# MachXO2_eval.net
KiCad netlist of a schematic drawn in EAGLE
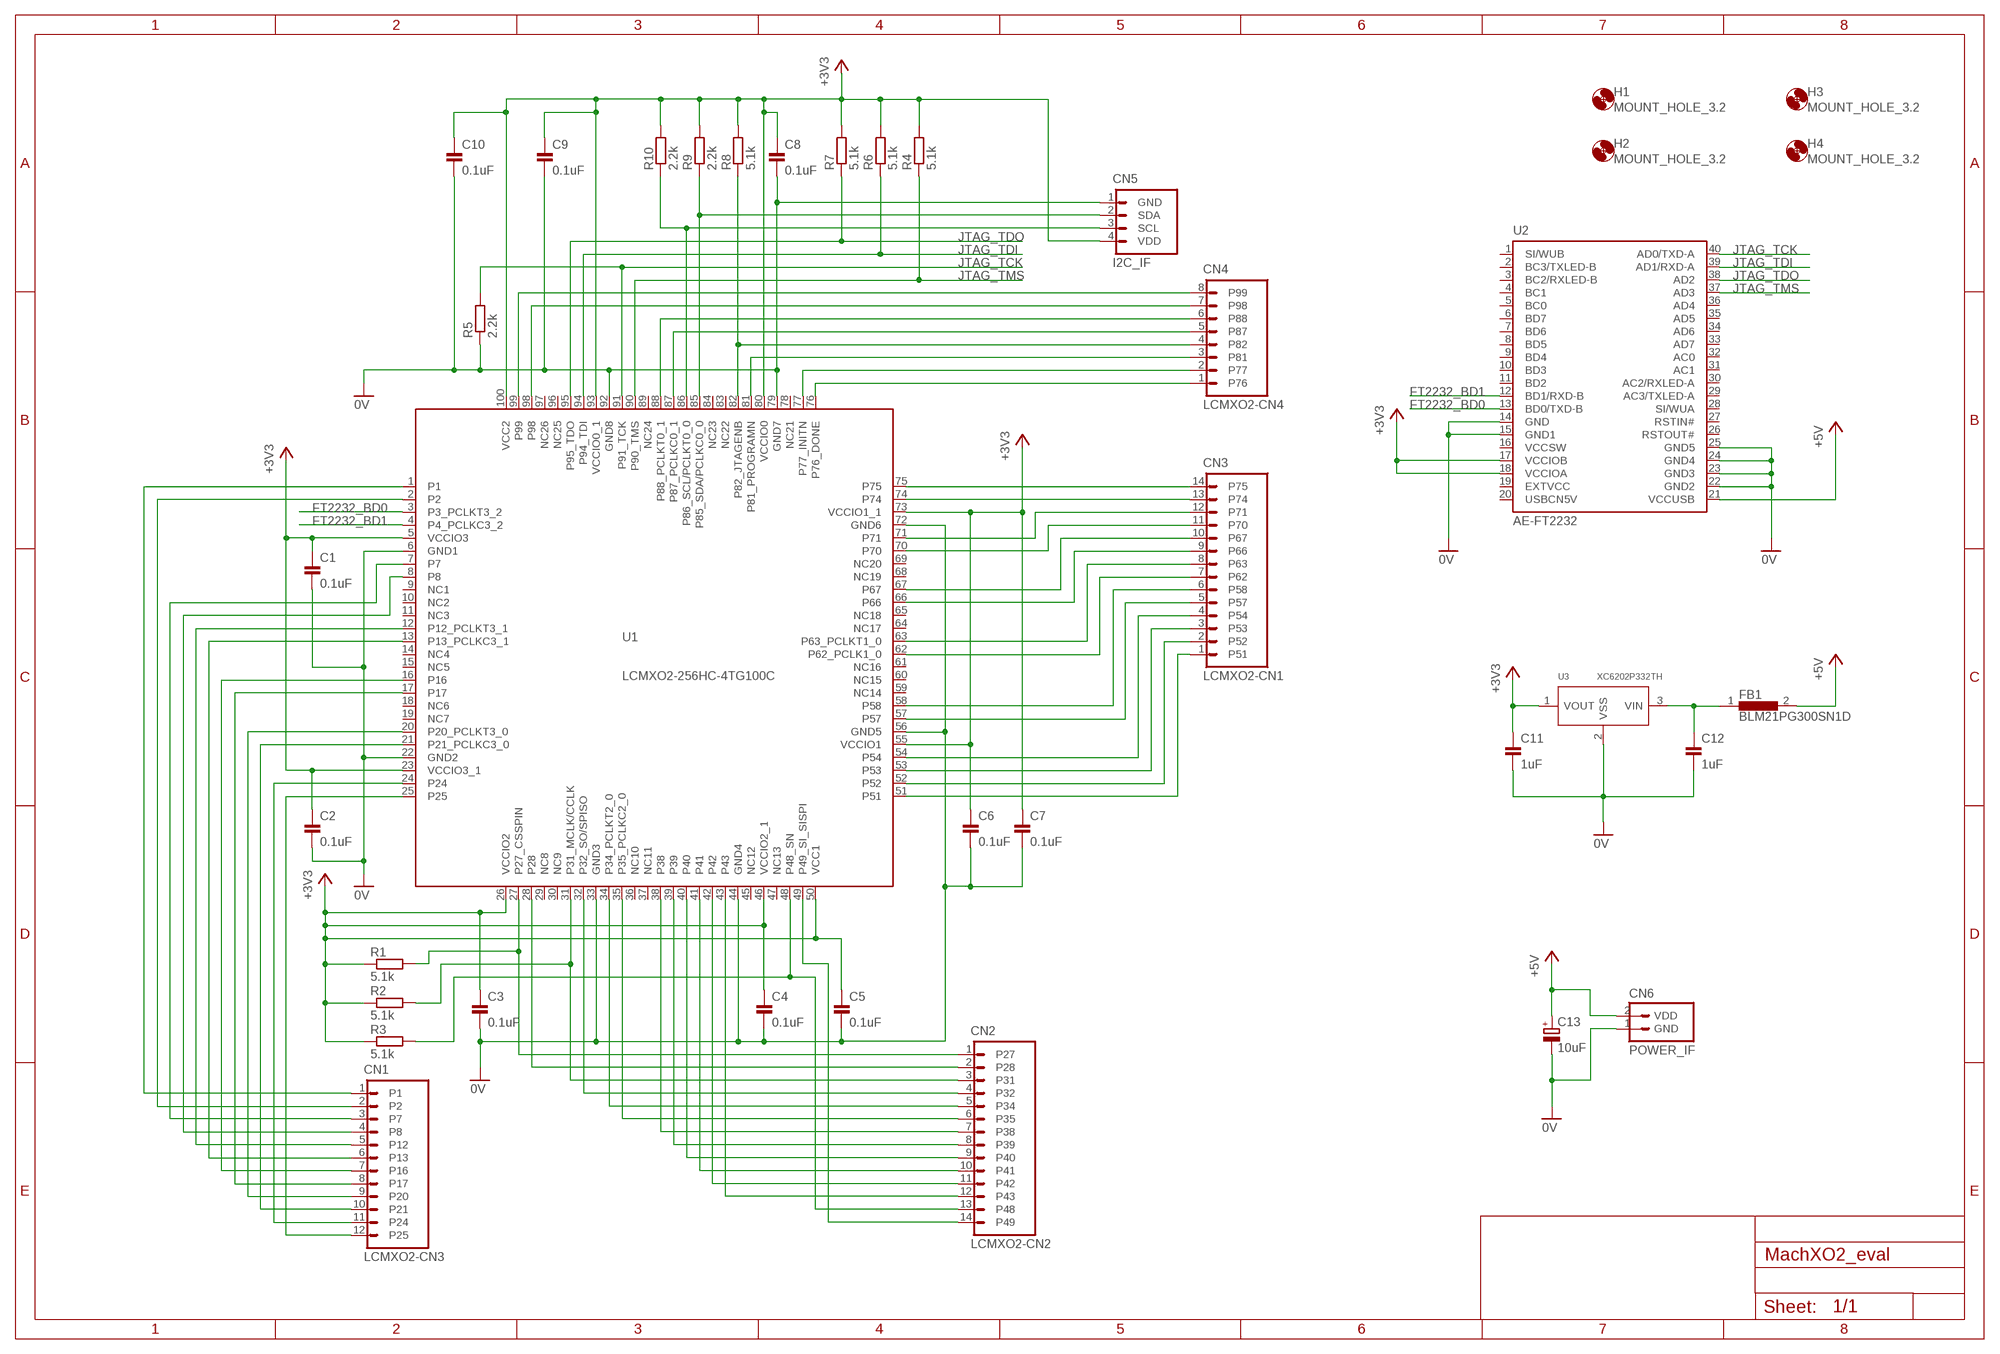
[diagram p0: schematic, sheet 1]

(export (version "E")
  (design (tool "Eeschema 10.0.6"))
  (components
    (comp (ref "C1")
      (value "0.1uF")
      (footprint "eagle-import:CAP_100MIL")
      (libsource (lib "eagle-import") (part "CAP_100MIL"))
    )
    (comp (ref "C2")
      (value "0.1uF")
      (footprint "eagle-import:CAP_100MIL")
      (libsource (lib "eagle-import") (part "CAP_100MIL"))
    )
    (comp (ref "C3")
      (value "0.1uF")
      (footprint "eagle-import:CAP_100MIL")
      (libsource (lib "eagle-import") (part "CAP_100MIL"))
    )
    (comp (ref "C4")
      (value "0.1uF")
      (footprint "eagle-import:CAP_100MIL")
      (libsource (lib "eagle-import") (part "CAP_100MIL"))
    )
    (comp (ref "C5")
      (value "0.1uF")
      (footprint "eagle-import:CAP_100MIL")
      (libsource (lib "eagle-import") (part "CAP_100MIL"))
    )
    (comp (ref "C6")
      (value "0.1uF")
      (footprint "eagle-import:CAP_100MIL")
      (libsource (lib "eagle-import") (part "CAP_100MIL"))
    )
    (comp (ref "C7")
      (value "0.1uF")
      (footprint "eagle-import:CAP_100MIL")
      (libsource (lib "eagle-import") (part "CAP_100MIL"))
    )
    (comp (ref "C8")
      (value "0.1uF")
      (footprint "eagle-import:CAP_100MIL")
      (libsource (lib "eagle-import") (part "CAP_100MIL"))
    )
    (comp (ref "C9")
      (value "0.1uF")
      (footprint "eagle-import:CAP_100MIL")
      (libsource (lib "eagle-import") (part "CAP_100MIL"))
    )
    (comp (ref "C10")
      (value "0.1uF")
      (footprint "eagle-import:CAP_100MIL")
      (libsource (lib "eagle-import") (part "CAP_100MIL"))
    )
    (comp (ref "C11")
      (value "1uF")
      (footprint "eagle-import:CAP_200MIL")
      (libsource (lib "eagle-import") (part "CAP_200MIL"))
    )
    (comp (ref "C12")
      (value "1uF")
      (footprint "eagle-import:CAP_200MIL")
      (libsource (lib "eagle-import") (part "CAP_200MIL"))
    )
    (comp (ref "C13")
      (value "10uF")
      (footprint "eagle-import:ELECAP_200MIL")
      (libsource (lib "eagle-import") (part "ELECAP_200MIL"))
    )
    (comp (ref "CN1")
      (value "LCMXO2-CN3")
      (footprint "eagle-import:LCMXO2-CN-3")
      (libsource (lib "eagle-import") (part "LCMXO2-CN3"))
    )
    (comp (ref "CN2")
      (value "LCMXO2-CN2")
      (footprint "eagle-import:LCMXO2-CN-2")
      (libsource (lib "eagle-import") (part "LCMXO2-CN2"))
    )
    (comp (ref "CN3")
      (value "LCMXO2-CN1")
      (footprint "eagle-import:LCMXO2-CN-1")
      (libsource (lib "eagle-import") (part "LCMXO2-CN1"))
    )
    (comp (ref "CN4")
      (value "LCMXO2-CN4")
      (footprint "eagle-import:LCMXO2-CN-4")
      (libsource (lib "eagle-import") (part "LCMXO2-CN4"))
    )
    (comp (ref "CN5")
      (value "I2C_IF")
      (footprint "eagle-import:I2C_IF_4PIN")
      (libsource (lib "eagle-import") (part "I2C_IF"))
    )
    (comp (ref "CN6")
      (value "POWER_IF")
      (footprint "eagle-import:HEADER_2PIN_POWER_IF")
      (libsource (lib "eagle-import") (part "POWER_IF"))
    )
    (comp (ref "FB1")
      (value "BLM21PG300SN1D")
      (footprint "eagle-import:SMD_2012")
      (libsource (lib "eagle-import") (part "BLM21PG300SN1D"))
    )
    (comp (ref "H1")
      (value "MOUNT_HOLE_3.2")
      (footprint "eagle-import:3,2")
      (libsource (lib "eagle-import") (part "MOUNT_HOLE_3.2"))
    )
    (comp (ref "H2")
      (value "MOUNT_HOLE_3.2")
      (footprint "eagle-import:3,2")
      (libsource (lib "eagle-import") (part "MOUNT_HOLE_3.2"))
    )
    (comp (ref "H3")
      (value "MOUNT_HOLE_3.2")
      (footprint "eagle-import:3,2")
      (libsource (lib "eagle-import") (part "MOUNT_HOLE_3.2"))
    )
    (comp (ref "H4")
      (value "MOUNT_HOLE_3.2")
      (footprint "eagle-import:3,2")
      (libsource (lib "eagle-import") (part "MOUNT_HOLE_3.2"))
    )
    (comp (ref "R1")
      (value "5.1k")
      (footprint "eagle-import:RESISTOR_0204_200MIL")
      (libsource (lib "eagle-import") (part "RESISTOR_200MIL"))
    )
    (comp (ref "R2")
      (value "5.1k")
      (footprint "eagle-import:RESISTOR_0204_200MIL")
      (libsource (lib "eagle-import") (part "RESISTOR_200MIL"))
    )
    (comp (ref "R3")
      (value "5.1k")
      (footprint "eagle-import:RESISTOR_0204_200MIL")
      (libsource (lib "eagle-import") (part "RESISTOR_200MIL"))
    )
    (comp (ref "R4")
      (value "5.1k")
      (footprint "eagle-import:RESISTOR_0204_200MIL")
      (libsource (lib "eagle-import") (part "RESISTOR_200MIL"))
    )
    (comp (ref "R5")
      (value "2.2k")
      (footprint "eagle-import:RESISTOR_0204_200MIL")
      (libsource (lib "eagle-import") (part "RESISTOR_200MIL"))
    )
    (comp (ref "R6")
      (value "5.1k")
      (footprint "eagle-import:RESISTOR_0204_200MIL")
      (libsource (lib "eagle-import") (part "RESISTOR_200MIL"))
    )
    (comp (ref "R7")
      (value "5.1k")
      (footprint "eagle-import:RESISTOR_0204_200MIL")
      (libsource (lib "eagle-import") (part "RESISTOR_200MIL"))
    )
    (comp (ref "R8")
      (value "5.1k")
      (footprint "eagle-import:RESISTOR_0204_200MIL")
      (libsource (lib "eagle-import") (part "RESISTOR_200MIL"))
    )
    (comp (ref "R9")
      (value "2.2k")
      (footprint "eagle-import:RESISTOR_0204_200MIL")
      (libsource (lib "eagle-import") (part "RESISTOR_200MIL"))
    )
    (comp (ref "R10")
      (value "2.2k")
      (footprint "eagle-import:RESISTOR_0204_200MIL")
      (libsource (lib "eagle-import") (part "RESISTOR_200MIL"))
    )
    (comp (ref "U1")
      (value "LCMXO2-256HC-4TG100C")
      (footprint "eagle-import:QFP100-0.5MMPITCH")
      (libsource (lib "eagle-import") (part "LCMXO2-256HC-4TG100C"))
    )
    (comp (ref "U2")
      (value "AE-FT2232")
      (footprint "eagle-import:DIL40")
      (libsource (lib "eagle-import") (part "AE-FT2232"))
    )
    (comp (ref "U3")
      (value "XC6202P332TH")
      (footprint "eagle-import:TO92-LINE")
      (libsource (lib "eagle-import") (part "XC6202P332TH"))
    )
  )
  (nets
    (net (code "1") (name "+3V3") (class "Default")
      (node (ref "C1") (pin "1") (pinfunction "1_1") (pintype "passive"))
      (node (ref "C10") (pin "1") (pinfunction "1_1") (pintype "passive"))
      (node (ref "C11") (pin "1") (pinfunction "1_1") (pintype "passive"))
      (node (ref "C2") (pin "1") (pinfunction "1_1") (pintype "passive"))
      (node (ref "C3") (pin "1") (pinfunction "1_1") (pintype "passive"))
      (node (ref "C4") (pin "1") (pinfunction "1_1") (pintype "passive"))
      (node (ref "C5") (pin "1") (pinfunction "1_1") (pintype "passive"))
      (node (ref "C6") (pin "1") (pinfunction "1_1") (pintype "passive"))
      (node (ref "C7") (pin "1") (pinfunction "1_1") (pintype "passive"))
      (node (ref "C8") (pin "1") (pinfunction "1_1") (pintype "passive"))
      (node (ref "C9") (pin "1") (pinfunction "1_1") (pintype "passive"))
      (node (ref "CN5") (pin "4") (pinfunction "VDD_4") (pintype "passive"))
      (node (ref "R1") (pin "1") (pinfunction "1_1") (pintype "passive"))
      (node (ref "R10") (pin "2") (pinfunction "2_2") (pintype "passive"))
      (node (ref "R2") (pin "1") (pinfunction "1_1") (pintype "passive"))
      (node (ref "R3") (pin "1") (pinfunction "1_1") (pintype "passive"))
      (node (ref "R4") (pin "2") (pinfunction "2_2") (pintype "passive"))
      (node (ref "R6") (pin "2") (pinfunction "2_2") (pintype "passive"))
      (node (ref "R7") (pin "2") (pinfunction "2_2") (pintype "passive"))
      (node (ref "R8") (pin "2") (pinfunction "2_2") (pintype "passive"))
      (node (ref "R9") (pin "2") (pinfunction "2_2") (pintype "passive"))
      (node (ref "U1") (pin "100") (pinfunction "VCC2_100") (pintype "passive"))
      (node (ref "U1") (pin "23") (pinfunction "VCCIO3_1_23") (pintype "passive"))
      (node (ref "U1") (pin "26") (pinfunction "VCCIO2_26") (pintype "passive"))
      (node (ref "U1") (pin "46") (pinfunction "VCCIO2_1_46") (pintype "passive"))
      (node (ref "U1") (pin "5") (pinfunction "VCCIO3_5") (pintype "passive"))
      (node (ref "U1") (pin "50") (pinfunction "VCC1_50") (pintype "passive"))
      (node (ref "U1") (pin "55") (pinfunction "VCCIO1_55") (pintype "passive"))
      (node (ref "U1") (pin "73") (pinfunction "VCCIO1_1_73") (pintype "passive"))
      (node (ref "U1") (pin "80") (pinfunction "VCCIO0_80") (pintype "passive"))
      (node (ref "U1") (pin "93") (pinfunction "VCCIO0_1_93") (pintype "passive"))
      (node (ref "U2") (pin "17") (pinfunction "VCCIOB_17") (pintype "passive"))
      (node (ref "U2") (pin "18") (pinfunction "VCCIOA_18") (pintype "passive"))
      (node (ref "U3") (pin "1") (pinfunction "VOUT_1") (pintype "passive"))
    )
    (net (code "2") (name "+5V") (class "Default")
      (node (ref "C13") (pin "+") (pinfunction "+_+") (pintype "passive"))
      (node (ref "CN6") (pin "2") (pinfunction "VDD_2") (pintype "passive"))
      (node (ref "FB1") (pin "2") (pinfunction "2_2") (pintype "passive"))
      (node (ref "U2") (pin "21") (pinfunction "VCCUSB_21") (pintype "passive"))
    )
    (net (code "3") (name "/FT2232_BD0") (class "Default")
      (node (ref "U1") (pin "3") (pinfunction "P3_PCLKT3_2_3") (pintype "bidirectional"))
      (node (ref "U2") (pin "13") (pinfunction "BD0/TXD-B_13") (pintype "bidirectional"))
    )
    (net (code "4") (name "/FT2232_BD1") (class "Default")
      (node (ref "U1") (pin "4") (pinfunction "P4_PCLKC3_2_4") (pintype "bidirectional"))
      (node (ref "U2") (pin "12") (pinfunction "BD1/RXD-B_12") (pintype "bidirectional"))
    )
    (net (code "5") (name "/JTAG_TCK") (class "Default")
      (node (ref "R5") (pin "2") (pinfunction "2_2") (pintype "passive"))
      (node (ref "U1") (pin "91") (pinfunction "P91_TCK_91") (pintype "bidirectional"))
      (node (ref "U2") (pin "40") (pinfunction "AD0/TXD-A_40") (pintype "bidirectional"))
    )
    (net (code "6") (name "/JTAG_TDI") (class "Default")
      (node (ref "R6") (pin "1") (pinfunction "1_1") (pintype "passive"))
      (node (ref "U1") (pin "94") (pinfunction "P94_TDI_94") (pintype "bidirectional"))
      (node (ref "U2") (pin "39") (pinfunction "AD1/RXD-A_39") (pintype "bidirectional"))
    )
    (net (code "7") (name "/JTAG_TDO") (class "Default")
      (node (ref "R7") (pin "1") (pinfunction "1_1") (pintype "passive"))
      (node (ref "U1") (pin "95") (pinfunction "P95_TDO_95") (pintype "bidirectional"))
      (node (ref "U2") (pin "38") (pinfunction "AD2_38") (pintype "bidirectional"))
    )
    (net (code "8") (name "/JTAG_TMS") (class "Default")
      (node (ref "R4") (pin "1") (pinfunction "1_1") (pintype "passive"))
      (node (ref "U1") (pin "90") (pinfunction "P90_TMS_90") (pintype "bidirectional"))
      (node (ref "U2") (pin "37") (pinfunction "AD3_37") (pintype "bidirectional"))
    )
    (net (code "9") (name "0V") (class "Default")
      (node (ref "C1") (pin "2") (pinfunction "2_2") (pintype "passive"))
      (node (ref "C10") (pin "2") (pinfunction "2_2") (pintype "passive"))
      (node (ref "C11") (pin "2") (pinfunction "2_2") (pintype "passive"))
      (node (ref "C12") (pin "2") (pinfunction "2_2") (pintype "passive"))
      (node (ref "C13") (pin "-") (pinfunction "-_-") (pintype "passive"))
      (node (ref "C2") (pin "2") (pinfunction "2_2") (pintype "passive"))
      (node (ref "C3") (pin "2") (pinfunction "2_2") (pintype "passive"))
      (node (ref "C4") (pin "2") (pinfunction "2_2") (pintype "passive"))
      (node (ref "C5") (pin "2") (pinfunction "2_2") (pintype "passive"))
      (node (ref "C6") (pin "2") (pinfunction "2_2") (pintype "passive"))
      (node (ref "C7") (pin "2") (pinfunction "2_2") (pintype "passive"))
      (node (ref "C8") (pin "2") (pinfunction "2_2") (pintype "passive"))
      (node (ref "C9") (pin "2") (pinfunction "2_2") (pintype "passive"))
      (node (ref "CN5") (pin "1") (pinfunction "GND_1") (pintype "passive"))
      (node (ref "CN6") (pin "1") (pinfunction "GND_1") (pintype "passive"))
      (node (ref "R5") (pin "1") (pinfunction "1_1") (pintype "passive"))
      (node (ref "U1") (pin "22") (pinfunction "GND2_22") (pintype "passive"))
      (node (ref "U1") (pin "33") (pinfunction "GND3_33") (pintype "passive"))
      (node (ref "U1") (pin "44") (pinfunction "GND4_44") (pintype "passive"))
      (node (ref "U1") (pin "56") (pinfunction "GND5_56") (pintype "passive"))
      (node (ref "U1") (pin "6") (pinfunction "GND1_6") (pintype "passive"))
      (node (ref "U1") (pin "72") (pinfunction "GND6_72") (pintype "passive"))
      (node (ref "U1") (pin "79") (pinfunction "GND7_79") (pintype "passive"))
      (node (ref "U1") (pin "92") (pinfunction "GND8_92") (pintype "passive"))
      (node (ref "U2") (pin "14") (pinfunction "GND_14") (pintype "passive"))
      (node (ref "U2") (pin "15") (pinfunction "GND1_15") (pintype "passive"))
      (node (ref "U2") (pin "22") (pinfunction "GND2_22") (pintype "passive"))
      (node (ref "U2") (pin "23") (pinfunction "GND3_23") (pintype "passive"))
      (node (ref "U2") (pin "24") (pinfunction "GND4_24") (pintype "passive"))
      (node (ref "U2") (pin "25") (pinfunction "GND5_25") (pintype "passive"))
      (node (ref "U3") (pin "2") (pinfunction "VSS_2") (pintype "passive"))
    )
    (net (code "10") (name "Net-(CN1-P1)") (class "Default")
      (node (ref "CN1") (pin "1") (pinfunction "P1_1") (pintype "bidirectional"))
      (node (ref "U1") (pin "1") (pinfunction "P1_1") (pintype "bidirectional"))
    )
    (net (code "11") (name "Net-(CN1-P2)") (class "Default")
      (node (ref "CN1") (pin "2") (pinfunction "P2_2") (pintype "bidirectional"))
      (node (ref "U1") (pin "2") (pinfunction "P2_2") (pintype "bidirectional"))
    )
    (net (code "12") (name "Net-(CN1-P7)") (class "Default")
      (node (ref "CN1") (pin "3") (pinfunction "P7_3") (pintype "bidirectional"))
      (node (ref "U1") (pin "7") (pinfunction "P7_7") (pintype "bidirectional"))
    )
    (net (code "13") (name "Net-(CN1-P8)") (class "Default")
      (node (ref "CN1") (pin "4") (pinfunction "P8_4") (pintype "bidirectional"))
      (node (ref "U1") (pin "8") (pinfunction "P8_8") (pintype "bidirectional"))
    )
    (net (code "14") (name "Net-(CN1-P12)") (class "Default")
      (node (ref "CN1") (pin "5") (pinfunction "P12_5") (pintype "bidirectional"))
      (node (ref "U1") (pin "12") (pinfunction "P12_PCLKT3_1_12") (pintype "bidirectional"))
    )
    (net (code "15") (name "Net-(CN1-P13)") (class "Default")
      (node (ref "CN1") (pin "6") (pinfunction "P13_6") (pintype "bidirectional"))
      (node (ref "U1") (pin "13") (pinfunction "P13_PCLKC3_1_13") (pintype "bidirectional"))
    )
    (net (code "16") (name "Net-(CN1-P16)") (class "Default")
      (node (ref "CN1") (pin "7") (pinfunction "P16_7") (pintype "bidirectional"))
      (node (ref "U1") (pin "16") (pinfunction "P16_16") (pintype "bidirectional"))
    )
    (net (code "17") (name "Net-(CN1-P17)") (class "Default")
      (node (ref "CN1") (pin "8") (pinfunction "P17_8") (pintype "bidirectional"))
      (node (ref "U1") (pin "17") (pinfunction "P17_17") (pintype "bidirectional"))
    )
    (net (code "18") (name "Net-(CN1-P20)") (class "Default")
      (node (ref "CN1") (pin "9") (pinfunction "P20_9") (pintype "bidirectional"))
      (node (ref "U1") (pin "20") (pinfunction "P20_PCLKT3_0_20") (pintype "bidirectional"))
    )
    (net (code "19") (name "Net-(CN1-P21)") (class "Default")
      (node (ref "CN1") (pin "10") (pinfunction "P21_10") (pintype "bidirectional"))
      (node (ref "U1") (pin "21") (pinfunction "P21_PCLKC3_0_21") (pintype "bidirectional"))
    )
    (net (code "20") (name "Net-(CN1-P24)") (class "Default")
      (node (ref "CN1") (pin "11") (pinfunction "P24_11") (pintype "bidirectional"))
      (node (ref "U1") (pin "24") (pinfunction "P24_24") (pintype "bidirectional"))
    )
    (net (code "21") (name "Net-(CN1-P25)") (class "Default")
      (node (ref "CN1") (pin "12") (pinfunction "P25_12") (pintype "bidirectional"))
      (node (ref "U1") (pin "25") (pinfunction "P25_25") (pintype "bidirectional"))
    )
    (net (code "22") (name "Net-(CN2-P27)") (class "Default")
      (node (ref "CN2") (pin "1") (pinfunction "P27_1") (pintype "bidirectional"))
      (node (ref "R1") (pin "2") (pinfunction "2_2") (pintype "passive"))
      (node (ref "U1") (pin "27") (pinfunction "P27_CSSPIN_27") (pintype "bidirectional"))
    )
    (net (code "23") (name "Net-(CN2-P28)") (class "Default")
      (node (ref "CN2") (pin "2") (pinfunction "P28_2") (pintype "bidirectional"))
      (node (ref "U1") (pin "28") (pinfunction "P28_28") (pintype "bidirectional"))
    )
    (net (code "24") (name "Net-(CN2-P31)") (class "Default")
      (node (ref "CN2") (pin "3") (pinfunction "P31_3") (pintype "bidirectional"))
      (node (ref "R2") (pin "2") (pinfunction "2_2") (pintype "passive"))
      (node (ref "U1") (pin "31") (pinfunction "P31_MCLK/CCLK_31") (pintype "bidirectional"))
    )
    (net (code "25") (name "Net-(CN2-P32)") (class "Default")
      (node (ref "CN2") (pin "4") (pinfunction "P32_4") (pintype "bidirectional"))
      (node (ref "U1") (pin "32") (pinfunction "P32_SO/SPISO_32") (pintype "bidirectional"))
    )
    (net (code "26") (name "Net-(CN2-P34)") (class "Default")
      (node (ref "CN2") (pin "5") (pinfunction "P34_5") (pintype "bidirectional"))
      (node (ref "U1") (pin "34") (pinfunction "P34_PCLKT2_0_34") (pintype "bidirectional"))
    )
    (net (code "27") (name "Net-(CN2-P35)") (class "Default")
      (node (ref "CN2") (pin "6") (pinfunction "P35_6") (pintype "bidirectional"))
      (node (ref "U1") (pin "35") (pinfunction "P35_PCLKC2_0_35") (pintype "bidirectional"))
    )
    (net (code "28") (name "Net-(CN2-P38)") (class "Default")
      (node (ref "CN2") (pin "7") (pinfunction "P38_7") (pintype "bidirectional"))
      (node (ref "U1") (pin "38") (pinfunction "P38_38") (pintype "bidirectional"))
    )
    (net (code "29") (name "Net-(CN2-P39)") (class "Default")
      (node (ref "CN2") (pin "8") (pinfunction "P39_8") (pintype "bidirectional"))
      (node (ref "U1") (pin "39") (pinfunction "P39_39") (pintype "bidirectional"))
    )
    (net (code "30") (name "Net-(CN2-P40)") (class "Default")
      (node (ref "CN2") (pin "9") (pinfunction "P40_9") (pintype "bidirectional"))
      (node (ref "U1") (pin "40") (pinfunction "P40_40") (pintype "bidirectional"))
    )
    (net (code "31") (name "Net-(CN2-P41)") (class "Default")
      (node (ref "CN2") (pin "10") (pinfunction "P41_10") (pintype "bidirectional"))
      (node (ref "U1") (pin "41") (pinfunction "P41_41") (pintype "bidirectional"))
    )
    (net (code "32") (name "Net-(CN2-P42)") (class "Default")
      (node (ref "CN2") (pin "11") (pinfunction "P42_11") (pintype "bidirectional"))
      (node (ref "U1") (pin "42") (pinfunction "P42_42") (pintype "bidirectional"))
    )
    (net (code "33") (name "Net-(CN2-P43)") (class "Default")
      (node (ref "CN2") (pin "12") (pinfunction "P43_12") (pintype "bidirectional"))
      (node (ref "U1") (pin "43") (pinfunction "P43_43") (pintype "bidirectional"))
    )
    (net (code "34") (name "Net-(CN2-P48)") (class "Default")
      (node (ref "CN2") (pin "13") (pinfunction "P48_13") (pintype "bidirectional"))
      (node (ref "R3") (pin "2") (pinfunction "2_2") (pintype "passive"))
      (node (ref "U1") (pin "48") (pinfunction "P48_SN_48") (pintype "bidirectional"))
    )
    (net (code "35") (name "Net-(CN2-P49)") (class "Default")
      (node (ref "CN2") (pin "14") (pinfunction "P49_14") (pintype "bidirectional"))
      (node (ref "U1") (pin "49") (pinfunction "P49_SI_SISPI_49") (pintype "bidirectional"))
    )
    (net (code "36") (name "Net-(CN3-P51)") (class "Default")
      (node (ref "CN3") (pin "1") (pinfunction "P51_1") (pintype "bidirectional"))
      (node (ref "U1") (pin "51") (pinfunction "P51_51") (pintype "bidirectional"))
    )
    (net (code "37") (name "Net-(CN3-P52)") (class "Default")
      (node (ref "CN3") (pin "2") (pinfunction "P52_2") (pintype "bidirectional"))
      (node (ref "U1") (pin "52") (pinfunction "P52_52") (pintype "bidirectional"))
    )
    (net (code "38") (name "Net-(CN3-P53)") (class "Default")
      (node (ref "CN3") (pin "3") (pinfunction "P53_3") (pintype "bidirectional"))
      (node (ref "U1") (pin "53") (pinfunction "P53_53") (pintype "bidirectional"))
    )
    (net (code "39") (name "Net-(CN3-P54)") (class "Default")
      (node (ref "CN3") (pin "4") (pinfunction "P54_4") (pintype "bidirectional"))
      (node (ref "U1") (pin "54") (pinfunction "P54_54") (pintype "bidirectional"))
    )
    (net (code "40") (name "Net-(CN3-P57)") (class "Default")
      (node (ref "CN3") (pin "5") (pinfunction "P57_5") (pintype "bidirectional"))
      (node (ref "U1") (pin "57") (pinfunction "P57_57") (pintype "bidirectional"))
    )
    (net (code "41") (name "Net-(CN3-P58)") (class "Default")
      (node (ref "CN3") (pin "6") (pinfunction "P58_6") (pintype "bidirectional"))
      (node (ref "U1") (pin "58") (pinfunction "P58_58") (pintype "bidirectional"))
    )
    (net (code "42") (name "Net-(CN3-P62)") (class "Default")
      (node (ref "CN3") (pin "7") (pinfunction "P62_7") (pintype "bidirectional"))
      (node (ref "U1") (pin "62") (pinfunction "P62_PCLK1_0_62") (pintype "bidirectional"))
    )
    (net (code "43") (name "Net-(CN3-P63)") (class "Default")
      (node (ref "CN3") (pin "8") (pinfunction "P63_8") (pintype "bidirectional"))
      (node (ref "U1") (pin "63") (pinfunction "P63_PCLKT1_0_63") (pintype "bidirectional"))
    )
    (net (code "44") (name "Net-(CN3-P66)") (class "Default")
      (node (ref "CN3") (pin "9") (pinfunction "P66_9") (pintype "bidirectional"))
      (node (ref "U1") (pin "66") (pinfunction "P66_66") (pintype "bidirectional"))
    )
    (net (code "45") (name "Net-(CN3-P67)") (class "Default")
      (node (ref "CN3") (pin "10") (pinfunction "P67_10") (pintype "bidirectional"))
      (node (ref "U1") (pin "67") (pinfunction "P67_67") (pintype "bidirectional"))
    )
    (net (code "46") (name "Net-(CN3-P70)") (class "Default")
      (node (ref "CN3") (pin "11") (pinfunction "P70_11") (pintype "bidirectional"))
      (node (ref "U1") (pin "70") (pinfunction "P70_70") (pintype "bidirectional"))
    )
    (net (code "47") (name "Net-(CN3-P71)") (class "Default")
      (node (ref "CN3") (pin "12") (pinfunction "P71_12") (pintype "bidirectional"))
      (node (ref "U1") (pin "71") (pinfunction "P71_71") (pintype "bidirectional"))
    )
    (net (code "48") (name "Net-(CN3-P74)") (class "Default")
      (node (ref "CN3") (pin "13") (pinfunction "P74_13") (pintype "bidirectional"))
      (node (ref "U1") (pin "74") (pinfunction "P74_74") (pintype "bidirectional"))
    )
    (net (code "49") (name "Net-(CN3-P75)") (class "Default")
      (node (ref "CN3") (pin "14") (pinfunction "P75_14") (pintype "bidirectional"))
      (node (ref "U1") (pin "75") (pinfunction "P75_75") (pintype "bidirectional"))
    )
    (net (code "50") (name "Net-(CN4-P76)") (class "Default")
      (node (ref "CN4") (pin "1") (pinfunction "P76_1") (pintype "bidirectional"))
      (node (ref "U1") (pin "76") (pinfunction "P76_DONE_76") (pintype "bidirectional"))
    )
    (net (code "51") (name "Net-(CN4-P77)") (class "Default")
      (node (ref "CN4") (pin "2") (pinfunction "P77_2") (pintype "bidirectional"))
      (node (ref "U1") (pin "77") (pinfunction "P77_INITN_77") (pintype "bidirectional"))
    )
    (net (code "52") (name "Net-(CN4-P81)") (class "Default")
      (node (ref "CN4") (pin "3") (pinfunction "P81_3") (pintype "bidirectional"))
      (node (ref "U1") (pin "81") (pinfunction "P81_PROGRAMN_81") (pintype "bidirectional"))
    )
    (net (code "53") (name "Net-(CN4-P82)") (class "Default")
      (node (ref "CN4") (pin "4") (pinfunction "P82_4") (pintype "bidirectional"))
      (node (ref "R8") (pin "1") (pinfunction "1_1") (pintype "passive"))
      (node (ref "U1") (pin "82") (pinfunction "P82_JTAGENB_82") (pintype "bidirectional"))
    )
    (net (code "54") (name "Net-(CN4-P87)") (class "Default")
      (node (ref "CN4") (pin "5") (pinfunction "P87_5") (pintype "bidirectional"))
      (node (ref "U1") (pin "87") (pinfunction "P87_PCLKC0_1_87") (pintype "bidirectional"))
    )
    (net (code "55") (name "Net-(CN4-P88)") (class "Default")
      (node (ref "CN4") (pin "6") (pinfunction "P88_6") (pintype "bidirectional"))
      (node (ref "U1") (pin "88") (pinfunction "P88_PCLKT0_1_88") (pintype "bidirectional"))
    )
    (net (code "56") (name "Net-(CN4-P98)") (class "Default")
      (node (ref "CN4") (pin "7") (pinfunction "P98_7") (pintype "bidirectional"))
      (node (ref "U1") (pin "98") (pinfunction "P98_98") (pintype "bidirectional"))
    )
    (net (code "57") (name "Net-(CN4-P99)") (class "Default")
      (node (ref "CN4") (pin "8") (pinfunction "P99_8") (pintype "bidirectional"))
      (node (ref "U1") (pin "99") (pinfunction "P99_99") (pintype "bidirectional"))
    )
    (net (code "58") (name "Net-(CN5-SCL)") (class "Default")
      (node (ref "CN5") (pin "3") (pinfunction "SCL_3") (pintype "bidirectional"))
      (node (ref "R10") (pin "1") (pinfunction "1_1") (pintype "passive"))
      (node (ref "U1") (pin "86") (pinfunction "P86_SCL/PCLKT0_0_86") (pintype "bidirectional"))
    )
    (net (code "59") (name "Net-(CN5-SDA)") (class "Default")
      (node (ref "CN5") (pin "2") (pinfunction "SDA_2") (pintype "bidirectional"))
      (node (ref "R9") (pin "1") (pinfunction "1_1") (pintype "passive"))
      (node (ref "U1") (pin "85") (pinfunction "P85_SDA/PCLKC0_0_85") (pintype "bidirectional"))
    )
    (net (code "60") (name "Net-(U3-VIN)") (class "Default")
      (node (ref "C12") (pin "1") (pinfunction "1_1") (pintype "passive"))
      (node (ref "FB1") (pin "1") (pinfunction "1_1") (pintype "passive"))
      (node (ref "U3") (pin "3") (pinfunction "VIN_3") (pintype "passive"))
    )
    (net (code "61") (name "unconnected-(U1-NC1-Pad9)") (class "Default")
      (node (ref "U1") (pin "9") (pinfunction "NC1_9") (pintype "no_connect"))
    )
    (net (code "62") (name "unconnected-(U1-NC2-Pad10)") (class "Default")
      (node (ref "U1") (pin "10") (pinfunction "NC2_10") (pintype "no_connect"))
    )
    (net (code "63") (name "unconnected-(U1-NC3-Pad11)") (class "Default")
      (node (ref "U1") (pin "11") (pinfunction "NC3_11") (pintype "no_connect"))
    )
    (net (code "64") (name "unconnected-(U1-NC4-Pad14)") (class "Default")
      (node (ref "U1") (pin "14") (pinfunction "NC4_14") (pintype "no_connect"))
    )
    (net (code "65") (name "unconnected-(U1-NC5-Pad15)") (class "Default")
      (node (ref "U1") (pin "15") (pinfunction "NC5_15") (pintype "no_connect"))
    )
    (net (code "66") (name "unconnected-(U1-NC6-Pad18)") (class "Default")
      (node (ref "U1") (pin "18") (pinfunction "NC6_18") (pintype "no_connect"))
    )
    (net (code "67") (name "unconnected-(U1-NC7-Pad19)") (class "Default")
      (node (ref "U1") (pin "19") (pinfunction "NC7_19") (pintype "no_connect"))
    )
    (net (code "68") (name "unconnected-(U1-NC8-Pad29)") (class "Default")
      (node (ref "U1") (pin "29") (pinfunction "NC8_29") (pintype "no_connect"))
    )
    (net (code "69") (name "unconnected-(U1-NC9-Pad30)") (class "Default")
      (node (ref "U1") (pin "30") (pinfunction "NC9_30") (pintype "no_connect"))
    )
    (net (code "70") (name "unconnected-(U1-NC10-Pad36)") (class "Default")
      (node (ref "U1") (pin "36") (pinfunction "NC10_36") (pintype "no_connect"))
    )
    (net (code "71") (name "unconnected-(U1-NC11-Pad37)") (class "Default")
      (node (ref "U1") (pin "37") (pinfunction "NC11_37") (pintype "no_connect"))
    )
    (net (code "72") (name "unconnected-(U1-NC12-Pad45)") (class "Default")
      (node (ref "U1") (pin "45") (pinfunction "NC12_45") (pintype "no_connect"))
    )
    (net (code "73") (name "unconnected-(U1-NC13-Pad47)") (class "Default")
      (node (ref "U1") (pin "47") (pinfunction "NC13_47") (pintype "no_connect"))
    )
    (net (code "74") (name "unconnected-(U1-NC14-Pad59)") (class "Default")
      (node (ref "U1") (pin "59") (pinfunction "NC14_59") (pintype "no_connect"))
    )
    (net (code "75") (name "unconnected-(U1-NC15-Pad60)") (class "Default")
      (node (ref "U1") (pin "60") (pinfunction "NC15_60") (pintype "no_connect"))
    )
    (net (code "76") (name "unconnected-(U1-NC16-Pad61)") (class "Default")
      (node (ref "U1") (pin "61") (pinfunction "NC16_61") (pintype "no_connect"))
    )
    (net (code "77") (name "unconnected-(U1-NC17-Pad64)") (class "Default")
      (node (ref "U1") (pin "64") (pinfunction "NC17_64") (pintype "no_connect"))
    )
    (net (code "78") (name "unconnected-(U1-NC18-Pad65)") (class "Default")
      (node (ref "U1") (pin "65") (pinfunction "NC18_65") (pintype "no_connect"))
    )
    (net (code "79") (name "unconnected-(U1-NC19-Pad68)") (class "Default")
      (node (ref "U1") (pin "68") (pinfunction "NC19_68") (pintype "no_connect"))
    )
    (net (code "80") (name "unconnected-(U1-NC20-Pad69)") (class "Default")
      (node (ref "U1") (pin "69") (pinfunction "NC20_69") (pintype "no_connect"))
    )
    (net (code "81") (name "unconnected-(U1-NC21-Pad78)") (class "Default")
      (node (ref "U1") (pin "78") (pinfunction "NC21_78") (pintype "no_connect"))
    )
    (net (code "82") (name "unconnected-(U1-NC22-Pad83)") (class "Default")
      (node (ref "U1") (pin "83") (pinfunction "NC22_83") (pintype "no_connect"))
    )
    (net (code "83") (name "unconnected-(U1-NC23-Pad84)") (class "Default")
      (node (ref "U1") (pin "84") (pinfunction "NC23_84") (pintype "no_connect"))
    )
    (net (code "84") (name "unconnected-(U1-NC24-Pad89)") (class "Default")
      (node (ref "U1") (pin "89") (pinfunction "NC24_89") (pintype "no_connect"))
    )
    (net (code "85") (name "unconnected-(U1-NC25-Pad96)") (class "Default")
      (node (ref "U1") (pin "96") (pinfunction "NC25_96") (pintype "no_connect"))
    )
    (net (code "86") (name "unconnected-(U1-NC26-Pad97)") (class "Default")
      (node (ref "U1") (pin "97") (pinfunction "NC26_97") (pintype "no_connect"))
    )
    (net (code "87") (name "unconnected-(U2-AC0-Pad32)") (class "Default")
      (node (ref "U2") (pin "32") (pinfunction "AC0_32") (pintype "bidirectional"))
    )
    (net (code "88") (name "unconnected-(U2-AC1-Pad31)") (class "Default")
      (node (ref "U2") (pin "31") (pinfunction "AC1_31") (pintype "bidirectional"))
    )
    (net (code "89") (name "unconnected-(U2-AC2{slash}RXLED-A-Pad30)") (class "Default")
      (node (ref "U2") (pin "30") (pinfunction "AC2/RXLED-A_30") (pintype "bidirectional"))
    )
    (net (code "90") (name "unconnected-(U2-AC3{slash}TXLED-A-Pad29)") (class "Default")
      (node (ref "U2") (pin "29") (pinfunction "AC3/TXLED-A_29") (pintype "bidirectional"))
    )
    (net (code "91") (name "unconnected-(U2-AD4-Pad36)") (class "Default")
      (node (ref "U2") (pin "36") (pinfunction "AD4_36") (pintype "bidirectional"))
    )
    (net (code "92") (name "unconnected-(U2-AD5-Pad35)") (class "Default")
      (node (ref "U2") (pin "35") (pinfunction "AD5_35") (pintype "bidirectional"))
    )
    (net (code "93") (name "unconnected-(U2-AD6-Pad34)") (class "Default")
      (node (ref "U2") (pin "34") (pinfunction "AD6_34") (pintype "bidirectional"))
    )
    (net (code "94") (name "unconnected-(U2-AD7-Pad33)") (class "Default")
      (node (ref "U2") (pin "33") (pinfunction "AD7_33") (pintype "bidirectional"))
    )
    (net (code "95") (name "unconnected-(U2-BC0-Pad5)") (class "Default")
      (node (ref "U2") (pin "5") (pinfunction "BC0_5") (pintype "bidirectional"))
    )
    (net (code "96") (name "unconnected-(U2-BC1-Pad4)") (class "Default")
      (node (ref "U2") (pin "4") (pinfunction "BC1_4") (pintype "bidirectional"))
    )
    (net (code "97") (name "unconnected-(U2-BC2{slash}RXLED-B-Pad3)") (class "Default")
      (node (ref "U2") (pin "3") (pinfunction "BC2/RXLED-B_3") (pintype "bidirectional"))
    )
    (net (code "98") (name "unconnected-(U2-BC3{slash}TXLED-B-Pad2)") (class "Default")
      (node (ref "U2") (pin "2") (pinfunction "BC3/TXLED-B_2") (pintype "bidirectional"))
    )
    (net (code "99") (name "unconnected-(U2-BD2-Pad11)") (class "Default")
      (node (ref "U2") (pin "11") (pinfunction "BD2_11") (pintype "bidirectional"))
    )
    (net (code "100") (name "unconnected-(U2-BD3-Pad10)") (class "Default")
      (node (ref "U2") (pin "10") (pinfunction "BD3_10") (pintype "bidirectional"))
    )
    (net (code "101") (name "unconnected-(U2-BD4-Pad9)") (class "Default")
      (node (ref "U2") (pin "9") (pinfunction "BD4_9") (pintype "bidirectional"))
    )
    (net (code "102") (name "unconnected-(U2-BD5-Pad8)") (class "Default")
      (node (ref "U2") (pin "8") (pinfunction "BD5_8") (pintype "bidirectional"))
    )
    (net (code "103") (name "unconnected-(U2-BD6-Pad7)") (class "Default")
      (node (ref "U2") (pin "7") (pinfunction "BD6_7") (pintype "bidirectional"))
    )
    (net (code "104") (name "unconnected-(U2-BD7-Pad6)") (class "Default")
      (node (ref "U2") (pin "6") (pinfunction "BD7_6") (pintype "bidirectional"))
    )
    (net (code "105") (name "unconnected-(U2-EXTVCC-Pad19)") (class "Default")
      (node (ref "U2") (pin "19") (pinfunction "EXTVCC_19") (pintype "passive"))
    )
    (net (code "106") (name "unconnected-(U2-RSTIN#-Pad27)") (class "Default")
      (node (ref "U2") (pin "27") (pinfunction "RSTIN#_27") (pintype "bidirectional"))
    )
    (net (code "107") (name "unconnected-(U2-RSTOUT#-Pad26)") (class "Default")
      (node (ref "U2") (pin "26") (pinfunction "RSTOUT#_26") (pintype "bidirectional"))
    )
    (net (code "108") (name "unconnected-(U2-SI{slash}WUA-Pad28)") (class "Default")
      (node (ref "U2") (pin "28") (pinfunction "SI/WUA_28") (pintype "bidirectional"))
    )
    (net (code "109") (name "unconnected-(U2-SI{slash}WUB-Pad1)") (class "Default")
      (node (ref "U2") (pin "1") (pinfunction "SI/WUB_1") (pintype "bidirectional"))
    )
    (net (code "110") (name "unconnected-(U2-USBCN5V-Pad20)") (class "Default")
      (node (ref "U2") (pin "20") (pinfunction "USBCN5V_20") (pintype "passive"))
    )
    (net (code "111") (name "unconnected-(U2-VCCSW-Pad16)") (class "Default")
      (node (ref "U2") (pin "16") (pinfunction "VCCSW_16") (pintype "passive"))
    )
  )
)
